# split36_left.net
KiCad netlist of a schematic drawn in EasyEDA Pro
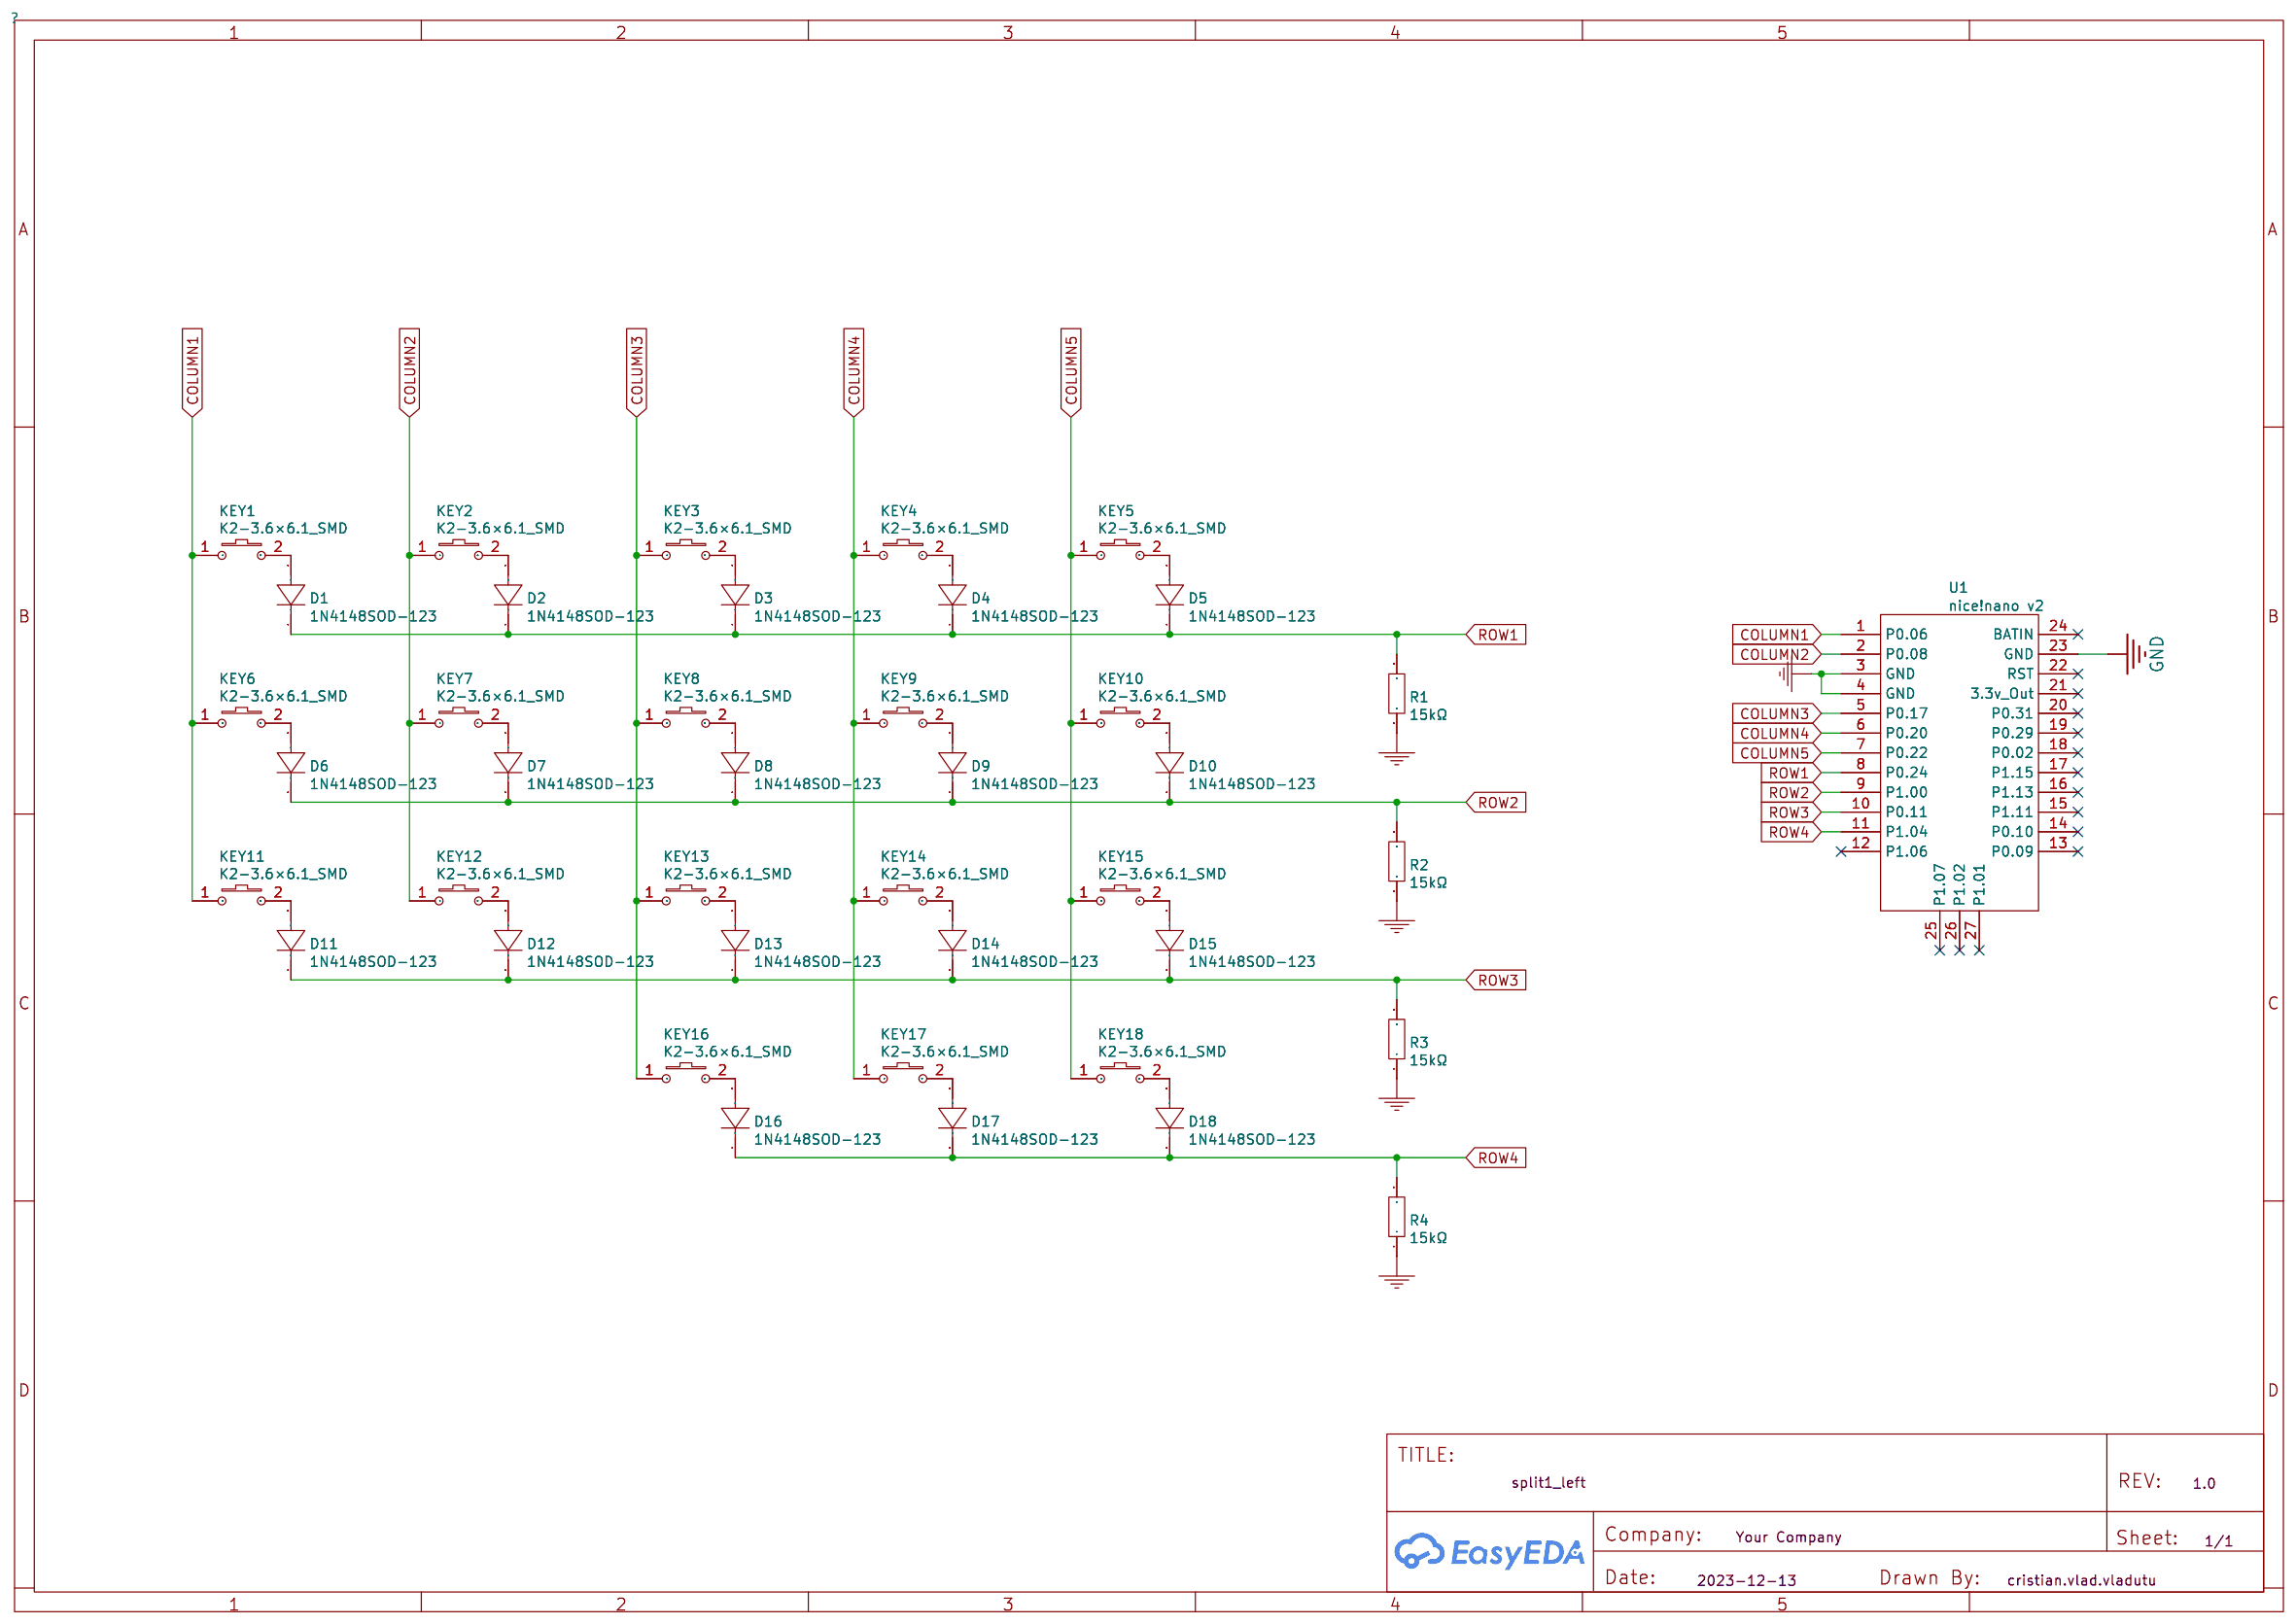
[diagram p0: schematic sheet]

(export (version "E")
  (design (tool "Eeschema 10.0.6"))
  (components
    (comp (ref "D1")
      (value "1N4148SOD-123")
      (footprint "easyedapro:SOD-123_L2.6-W1.6-LS3.5-RD")
      (fields (field (name "Manufacturer") "JKSEMI(金开盛)"))
      (libsource (lib "easyedapro") (part "1N4148SOD-123"))
    )
    (comp (ref "D2")
      (value "1N4148SOD-123")
      (footprint "easyedapro:SOD-123_L2.6-W1.6-LS3.5-RD")
      (fields (field (name "Manufacturer") "JKSEMI(金开盛)"))
      (libsource (lib "easyedapro") (part "1N4148SOD-123"))
    )
    (comp (ref "D3")
      (value "1N4148SOD-123")
      (footprint "easyedapro:SOD-123_L2.6-W1.6-LS3.5-RD")
      (fields (field (name "Manufacturer") "JKSEMI(金开盛)"))
      (libsource (lib "easyedapro") (part "1N4148SOD-123"))
    )
    (comp (ref "D4")
      (value "1N4148SOD-123")
      (footprint "easyedapro:SOD-123_L2.6-W1.6-LS3.5-RD")
      (fields (field (name "Manufacturer") "JKSEMI(金开盛)"))
      (libsource (lib "easyedapro") (part "1N4148SOD-123"))
    )
    (comp (ref "D5")
      (value "1N4148SOD-123")
      (footprint "easyedapro:SOD-123_L2.6-W1.6-LS3.5-RD")
      (fields (field (name "Manufacturer") "JKSEMI(金开盛)"))
      (libsource (lib "easyedapro") (part "1N4148SOD-123"))
    )
    (comp (ref "D6")
      (value "1N4148SOD-123")
      (footprint "easyedapro:SOD-123_L2.6-W1.6-LS3.5-RD")
      (fields (field (name "Manufacturer") "JKSEMI(金开盛)"))
      (libsource (lib "easyedapro") (part "1N4148SOD-123"))
    )
    (comp (ref "D7")
      (value "1N4148SOD-123")
      (footprint "easyedapro:SOD-123_L2.6-W1.6-LS3.5-RD")
      (fields (field (name "Manufacturer") "JKSEMI(金开盛)"))
      (libsource (lib "easyedapro") (part "1N4148SOD-123"))
    )
    (comp (ref "D8")
      (value "1N4148SOD-123")
      (footprint "easyedapro:SOD-123_L2.6-W1.6-LS3.5-RD")
      (fields (field (name "Manufacturer") "JKSEMI(金开盛)"))
      (libsource (lib "easyedapro") (part "1N4148SOD-123"))
    )
    (comp (ref "D9")
      (value "1N4148SOD-123")
      (footprint "easyedapro:SOD-123_L2.6-W1.6-LS3.5-RD")
      (fields (field (name "Manufacturer") "JKSEMI(金开盛)"))
      (libsource (lib "easyedapro") (part "1N4148SOD-123"))
    )
    (comp (ref "D10")
      (value "1N4148SOD-123")
      (footprint "easyedapro:SOD-123_L2.6-W1.6-LS3.5-RD")
      (fields (field (name "Manufacturer") "JKSEMI(金开盛)"))
      (libsource (lib "easyedapro") (part "1N4148SOD-123"))
    )
    (comp (ref "D11")
      (value "1N4148SOD-123")
      (footprint "easyedapro:SOD-123_L2.6-W1.6-LS3.5-RD")
      (fields (field (name "Manufacturer") "JKSEMI(金开盛)"))
      (libsource (lib "easyedapro") (part "1N4148SOD-123"))
    )
    (comp (ref "D12")
      (value "1N4148SOD-123")
      (footprint "easyedapro:SOD-123_L2.6-W1.6-LS3.5-RD")
      (fields (field (name "Manufacturer") "JKSEMI(金开盛)"))
      (libsource (lib "easyedapro") (part "1N4148SOD-123"))
    )
    (comp (ref "D13")
      (value "1N4148SOD-123")
      (footprint "easyedapro:SOD-123_L2.6-W1.6-LS3.5-RD")
      (fields (field (name "Manufacturer") "JKSEMI(金开盛)"))
      (libsource (lib "easyedapro") (part "1N4148SOD-123"))
    )
    (comp (ref "D14")
      (value "1N4148SOD-123")
      (footprint "easyedapro:SOD-123_L2.6-W1.6-LS3.5-RD")
      (fields (field (name "Manufacturer") "JKSEMI(金开盛)"))
      (libsource (lib "easyedapro") (part "1N4148SOD-123"))
    )
    (comp (ref "D15")
      (value "1N4148SOD-123")
      (footprint "easyedapro:SOD-123_L2.6-W1.6-LS3.5-RD")
      (fields (field (name "Manufacturer") "JKSEMI(金开盛)"))
      (libsource (lib "easyedapro") (part "1N4148SOD-123"))
    )
    (comp (ref "D16")
      (value "1N4148SOD-123")
      (footprint "easyedapro:SOD-123_L2.6-W1.6-LS3.5-RD")
      (fields (field (name "Manufacturer") "JKSEMI(金开盛)"))
      (libsource (lib "easyedapro") (part "1N4148SOD-123"))
    )
    (comp (ref "D17")
      (value "1N4148SOD-123")
      (footprint "easyedapro:SOD-123_L2.6-W1.6-LS3.5-RD")
      (fields (field (name "Manufacturer") "JKSEMI(金开盛)"))
      (libsource (lib "easyedapro") (part "1N4148SOD-123"))
    )
    (comp (ref "D18")
      (value "1N4148SOD-123")
      (footprint "easyedapro:SOD-123_L2.6-W1.6-LS3.5-RD")
      (fields (field (name "Manufacturer") "JKSEMI(金开盛)"))
      (libsource (lib "easyedapro") (part "1N4148SOD-123"))
    )
    (comp (ref "KEY1")
      (value "K2-3.6×6.1_SMD")
      (footprint "easyedapro:GATERON LOW PROFILE SWITCH HOTSWAP LED")
      (fields (field (name "Manufacturer Part") "K2-1107ST-A4SW-06"))
      (libsource (lib "easyedapro") (part "K2-3.6×6.1_SMD"))
    )
    (comp (ref "KEY2")
      (value "K2-3.6×6.1_SMD")
      (footprint "easyedapro:GATERON LOW PROFILE SWITCH HOTSWAP LED")
      (fields (field (name "Manufacturer Part") "K2-1107ST-A4SW-06"))
      (libsource (lib "easyedapro") (part "K2-3.6×6.1_SMD"))
    )
    (comp (ref "KEY3")
      (value "K2-3.6×6.1_SMD")
      (footprint "easyedapro:GATERON LOW PROFILE SWITCH HOTSWAP LED")
      (fields (field (name "Manufacturer Part") "K2-1107ST-A4SW-06"))
      (libsource (lib "easyedapro") (part "K2-3.6×6.1_SMD"))
    )
    (comp (ref "KEY4")
      (value "K2-3.6×6.1_SMD")
      (footprint "easyedapro:GATERON LOW PROFILE SWITCH HOTSWAP LED")
      (fields (field (name "Manufacturer Part") "K2-1107ST-A4SW-06"))
      (libsource (lib "easyedapro") (part "K2-3.6×6.1_SMD"))
    )
    (comp (ref "KEY5")
      (value "K2-3.6×6.1_SMD")
      (footprint "easyedapro:GATERON LOW PROFILE SWITCH HOTSWAP LED")
      (fields (field (name "Manufacturer Part") "K2-1107ST-A4SW-06"))
      (libsource (lib "easyedapro") (part "K2-3.6×6.1_SMD"))
    )
    (comp (ref "KEY6")
      (value "K2-3.6×6.1_SMD")
      (footprint "easyedapro:GATERON LOW PROFILE SWITCH HOTSWAP LED")
      (fields (field (name "Manufacturer Part") "K2-1107ST-A4SW-06"))
      (libsource (lib "easyedapro") (part "K2-3.6×6.1_SMD"))
    )
    (comp (ref "KEY7")
      (value "K2-3.6×6.1_SMD")
      (footprint "easyedapro:GATERON LOW PROFILE SWITCH HOTSWAP LED")
      (fields (field (name "Manufacturer Part") "K2-1107ST-A4SW-06"))
      (libsource (lib "easyedapro") (part "K2-3.6×6.1_SMD"))
    )
    (comp (ref "KEY8")
      (value "K2-3.6×6.1_SMD")
      (footprint "easyedapro:GATERON LOW PROFILE SWITCH HOTSWAP LED")
      (fields (field (name "Manufacturer Part") "K2-1107ST-A4SW-06"))
      (libsource (lib "easyedapro") (part "K2-3.6×6.1_SMD"))
    )
    (comp (ref "KEY9")
      (value "K2-3.6×6.1_SMD")
      (footprint "easyedapro:GATERON LOW PROFILE SWITCH HOTSWAP LED")
      (fields (field (name "Manufacturer Part") "K2-1107ST-A4SW-06"))
      (libsource (lib "easyedapro") (part "K2-3.6×6.1_SMD"))
    )
    (comp (ref "KEY10")
      (value "K2-3.6×6.1_SMD")
      (footprint "easyedapro:GATERON LOW PROFILE SWITCH HOTSWAP LED")
      (fields (field (name "Manufacturer Part") "K2-1107ST-A4SW-06"))
      (libsource (lib "easyedapro") (part "K2-3.6×6.1_SMD"))
    )
    (comp (ref "KEY11")
      (value "K2-3.6×6.1_SMD")
      (footprint "easyedapro:GATERON LOW PROFILE SWITCH HOTSWAP LED")
      (fields (field (name "Manufacturer Part") "K2-1107ST-A4SW-06"))
      (libsource (lib "easyedapro") (part "K2-3.6×6.1_SMD"))
    )
    (comp (ref "KEY12")
      (value "K2-3.6×6.1_SMD")
      (footprint "easyedapro:GATERON LOW PROFILE SWITCH HOTSWAP LED")
      (fields (field (name "Manufacturer Part") "K2-1107ST-A4SW-06"))
      (libsource (lib "easyedapro") (part "K2-3.6×6.1_SMD"))
    )
    (comp (ref "KEY13")
      (value "K2-3.6×6.1_SMD")
      (footprint "easyedapro:GATERON LOW PROFILE SWITCH HOTSWAP LED")
      (fields (field (name "Manufacturer Part") "K2-1107ST-A4SW-06"))
      (libsource (lib "easyedapro") (part "K2-3.6×6.1_SMD"))
    )
    (comp (ref "KEY14")
      (value "K2-3.6×6.1_SMD")
      (footprint "easyedapro:GATERON LOW PROFILE SWITCH HOTSWAP LED")
      (fields (field (name "Manufacturer Part") "K2-1107ST-A4SW-06"))
      (libsource (lib "easyedapro") (part "K2-3.6×6.1_SMD"))
    )
    (comp (ref "KEY15")
      (value "K2-3.6×6.1_SMD")
      (footprint "easyedapro:GATERON LOW PROFILE SWITCH HOTSWAP LED")
      (fields (field (name "Manufacturer Part") "K2-1107ST-A4SW-06"))
      (libsource (lib "easyedapro") (part "K2-3.6×6.1_SMD"))
    )
    (comp (ref "KEY16")
      (value "K2-3.6×6.1_SMD")
      (footprint "easyedapro:GATERON LOW PROFILE SWITCH HOTSWAP LED")
      (fields (field (name "Manufacturer Part") "K2-1107ST-A4SW-06"))
      (libsource (lib "easyedapro") (part "K2-3.6×6.1_SMD"))
    )
    (comp (ref "KEY17")
      (value "K2-3.6×6.1_SMD")
      (footprint "easyedapro:GATERON LOW PROFILE SWITCH HOTSWAP LED")
      (fields (field (name "Manufacturer Part") "K2-1107ST-A4SW-06"))
      (libsource (lib "easyedapro") (part "K2-3.6×6.1_SMD"))
    )
    (comp (ref "KEY18")
      (value "K2-3.6×6.1_SMD")
      (footprint "easyedapro:GATERON LOW PROFILE SWITCH HOTSWAP LED")
      (fields (field (name "Manufacturer Part") "K2-1107ST-A4SW-06"))
      (libsource (lib "easyedapro") (part "K2-3.6×6.1_SMD"))
    )
    (comp (ref "R1")
      (value "15kΩ")
      (footprint "easyedapro:R0402")
      (fields (field (name "Manufacturer Part") "RMC040215K5%N") (field (name "Manufacturer") "Tyohm(幸亚电阻)"))
      (libsource (lib "easyedapro") (part "15kΩ"))
    )
    (comp (ref "R2")
      (value "15kΩ")
      (footprint "easyedapro:R0402")
      (fields (field (name "Manufacturer Part") "RMC040215K5%N") (field (name "Manufacturer") "Tyohm(幸亚电阻)"))
      (libsource (lib "easyedapro") (part "15kΩ"))
    )
    (comp (ref "R3")
      (value "15kΩ")
      (footprint "easyedapro:R0402")
      (fields (field (name "Manufacturer Part") "RMC040215K5%N") (field (name "Manufacturer") "Tyohm(幸亚电阻)"))
      (libsource (lib "easyedapro") (part "15kΩ"))
    )
    (comp (ref "R4")
      (value "15kΩ")
      (footprint "easyedapro:R0402")
      (fields (field (name "Manufacturer Part") "RMC040215K5%N") (field (name "Manufacturer") "Tyohm(幸亚电阻)"))
      (libsource (lib "easyedapro") (part "15kΩ"))
    )
    (comp (ref "U1")
      (value "nice!nano v2")
      (footprint "easyedapro:NICE!NANO V2")
      (fields (field (name "Manufacturer") "nice!"))
      (libsource (lib "easyedapro") (part "nice!nano v2"))
    )
  )
  (nets
    (net (code "1") (name "COLUMN1") (class "Default")
      (node (ref "KEY1") (pin "1") (pinfunction "1_1") (pintype "unspecified"))
      (node (ref "KEY11") (pin "1") (pinfunction "1_1") (pintype "unspecified"))
      (node (ref "KEY6") (pin "1") (pinfunction "1_1") (pintype "unspecified"))
      (node (ref "U1") (pin "1") (pinfunction "P0.06_1") (pintype "input"))
    )
    (net (code "2") (name "COLUMN2") (class "Default")
      (node (ref "KEY12") (pin "1") (pinfunction "1_1") (pintype "unspecified"))
      (node (ref "KEY2") (pin "1") (pinfunction "1_1") (pintype "unspecified"))
      (node (ref "KEY7") (pin "1") (pinfunction "1_1") (pintype "unspecified"))
      (node (ref "U1") (pin "2") (pinfunction "P0.08_2") (pintype "input"))
    )
    (net (code "3") (name "COLUMN3") (class "Default")
      (node (ref "KEY13") (pin "1") (pinfunction "1_1") (pintype "unspecified"))
      (node (ref "KEY16") (pin "1") (pinfunction "1_1") (pintype "unspecified"))
      (node (ref "KEY3") (pin "1") (pinfunction "1_1") (pintype "unspecified"))
      (node (ref "KEY8") (pin "1") (pinfunction "1_1") (pintype "unspecified"))
      (node (ref "U1") (pin "5") (pinfunction "P0.17_5") (pintype "unspecified"))
    )
    (net (code "4") (name "COLUMN4") (class "Default")
      (node (ref "KEY14") (pin "1") (pinfunction "1_1") (pintype "unspecified"))
      (node (ref "KEY17") (pin "1") (pinfunction "1_1") (pintype "unspecified"))
      (node (ref "KEY4") (pin "1") (pinfunction "1_1") (pintype "unspecified"))
      (node (ref "KEY9") (pin "1") (pinfunction "1_1") (pintype "unspecified"))
      (node (ref "U1") (pin "6") (pinfunction "P0.20_6") (pintype "unspecified"))
    )
    (net (code "5") (name "COLUMN5") (class "Default")
      (node (ref "KEY10") (pin "1") (pinfunction "1_1") (pintype "unspecified"))
      (node (ref "KEY15") (pin "1") (pinfunction "1_1") (pintype "unspecified"))
      (node (ref "KEY18") (pin "1") (pinfunction "1_1") (pintype "unspecified"))
      (node (ref "KEY5") (pin "1") (pinfunction "1_1") (pintype "unspecified"))
      (node (ref "U1") (pin "7") (pinfunction "P0.22_7") (pintype "unspecified"))
    )
    (net (code "6") (name "GND") (class "Default")
      (node (ref "R1") (pin "1") (pinfunction "1_1") (pintype "unspecified"))
      (node (ref "R2") (pin "1") (pinfunction "1_1") (pintype "unspecified"))
      (node (ref "R3") (pin "1") (pinfunction "1_1") (pintype "unspecified"))
      (node (ref "R4") (pin "1") (pinfunction "1_1") (pintype "unspecified"))
      (node (ref "U1") (pin "23") (pinfunction "GND_23") (pintype "bidirectional"))
      (node (ref "U1") (pin "3") (pinfunction "GND_3") (pintype "unspecified"))
      (node (ref "U1") (pin "4") (pinfunction "GND_4") (pintype "unspecified"))
    )
    (net (code "7") (name "Net-(D1-A)") (class "Default")
      (node (ref "D1") (pin "2") (pinfunction "A_2") (pintype "unspecified"))
      (node (ref "KEY1") (pin "2") (pinfunction "2_2") (pintype "unspecified"))
    )
    (net (code "8") (name "Net-(D2-A)") (class "Default")
      (node (ref "D2") (pin "2") (pinfunction "A_2") (pintype "unspecified"))
      (node (ref "KEY2") (pin "2") (pinfunction "2_2") (pintype "unspecified"))
    )
    (net (code "9") (name "Net-(D3-A)") (class "Default")
      (node (ref "D3") (pin "2") (pinfunction "A_2") (pintype "unspecified"))
      (node (ref "KEY3") (pin "2") (pinfunction "2_2") (pintype "unspecified"))
    )
    (net (code "10") (name "Net-(D4-A)") (class "Default")
      (node (ref "D4") (pin "2") (pinfunction "A_2") (pintype "unspecified"))
      (node (ref "KEY4") (pin "2") (pinfunction "2_2") (pintype "unspecified"))
    )
    (net (code "11") (name "Net-(D5-A)") (class "Default")
      (node (ref "D5") (pin "2") (pinfunction "A_2") (pintype "unspecified"))
      (node (ref "KEY5") (pin "2") (pinfunction "2_2") (pintype "unspecified"))
    )
    (net (code "12") (name "Net-(D6-A)") (class "Default")
      (node (ref "D6") (pin "2") (pinfunction "A_2") (pintype "unspecified"))
      (node (ref "KEY6") (pin "2") (pinfunction "2_2") (pintype "unspecified"))
    )
    (net (code "13") (name "Net-(D7-A)") (class "Default")
      (node (ref "D7") (pin "2") (pinfunction "A_2") (pintype "unspecified"))
      (node (ref "KEY7") (pin "2") (pinfunction "2_2") (pintype "unspecified"))
    )
    (net (code "14") (name "Net-(D8-A)") (class "Default")
      (node (ref "D8") (pin "2") (pinfunction "A_2") (pintype "unspecified"))
      (node (ref "KEY8") (pin "2") (pinfunction "2_2") (pintype "unspecified"))
    )
    (net (code "15") (name "Net-(D9-A)") (class "Default")
      (node (ref "D9") (pin "2") (pinfunction "A_2") (pintype "unspecified"))
      (node (ref "KEY9") (pin "2") (pinfunction "2_2") (pintype "unspecified"))
    )
    (net (code "16") (name "Net-(D10-A)") (class "Default")
      (node (ref "D10") (pin "2") (pinfunction "A_2") (pintype "unspecified"))
      (node (ref "KEY10") (pin "2") (pinfunction "2_2") (pintype "unspecified"))
    )
    (net (code "17") (name "Net-(D11-A)") (class "Default")
      (node (ref "D11") (pin "2") (pinfunction "A_2") (pintype "unspecified"))
      (node (ref "KEY11") (pin "2") (pinfunction "2_2") (pintype "unspecified"))
    )
    (net (code "18") (name "Net-(D12-A)") (class "Default")
      (node (ref "D12") (pin "2") (pinfunction "A_2") (pintype "unspecified"))
      (node (ref "KEY12") (pin "2") (pinfunction "2_2") (pintype "unspecified"))
    )
    (net (code "19") (name "Net-(D13-A)") (class "Default")
      (node (ref "D13") (pin "2") (pinfunction "A_2") (pintype "unspecified"))
      (node (ref "KEY13") (pin "2") (pinfunction "2_2") (pintype "unspecified"))
    )
    (net (code "20") (name "Net-(D14-A)") (class "Default")
      (node (ref "D14") (pin "2") (pinfunction "A_2") (pintype "unspecified"))
      (node (ref "KEY14") (pin "2") (pinfunction "2_2") (pintype "unspecified"))
    )
    (net (code "21") (name "Net-(D15-A)") (class "Default")
      (node (ref "D15") (pin "2") (pinfunction "A_2") (pintype "unspecified"))
      (node (ref "KEY15") (pin "2") (pinfunction "2_2") (pintype "unspecified"))
    )
    (net (code "22") (name "Net-(D16-A)") (class "Default")
      (node (ref "D16") (pin "2") (pinfunction "A_2") (pintype "unspecified"))
      (node (ref "KEY16") (pin "2") (pinfunction "2_2") (pintype "unspecified"))
    )
    (net (code "23") (name "Net-(D17-A)") (class "Default")
      (node (ref "D17") (pin "2") (pinfunction "A_2") (pintype "unspecified"))
      (node (ref "KEY17") (pin "2") (pinfunction "2_2") (pintype "unspecified"))
    )
    (net (code "24") (name "Net-(D18-A)") (class "Default")
      (node (ref "D18") (pin "2") (pinfunction "A_2") (pintype "unspecified"))
      (node (ref "KEY18") (pin "2") (pinfunction "2_2") (pintype "unspecified"))
    )
    (net (code "25") (name "ROW1") (class "Default")
      (node (ref "D1") (pin "1") (pinfunction "K_1") (pintype "unspecified"))
      (node (ref "D2") (pin "1") (pinfunction "K_1") (pintype "unspecified"))
      (node (ref "D3") (pin "1") (pinfunction "K_1") (pintype "unspecified"))
      (node (ref "D4") (pin "1") (pinfunction "K_1") (pintype "unspecified"))
      (node (ref "D5") (pin "1") (pinfunction "K_1") (pintype "unspecified"))
      (node (ref "R1") (pin "2") (pinfunction "2_2") (pintype "unspecified"))
      (node (ref "U1") (pin "8") (pinfunction "P0.24_8") (pintype "unspecified"))
    )
    (net (code "26") (name "ROW2") (class "Default")
      (node (ref "D10") (pin "1") (pinfunction "K_1") (pintype "unspecified"))
      (node (ref "D6") (pin "1") (pinfunction "K_1") (pintype "unspecified"))
      (node (ref "D7") (pin "1") (pinfunction "K_1") (pintype "unspecified"))
      (node (ref "D8") (pin "1") (pinfunction "K_1") (pintype "unspecified"))
      (node (ref "D9") (pin "1") (pinfunction "K_1") (pintype "unspecified"))
      (node (ref "R2") (pin "2") (pinfunction "2_2") (pintype "unspecified"))
      (node (ref "U1") (pin "9") (pinfunction "P1.00_9") (pintype "unspecified"))
    )
    (net (code "27") (name "ROW3") (class "Default")
      (node (ref "D11") (pin "1") (pinfunction "K_1") (pintype "unspecified"))
      (node (ref "D12") (pin "1") (pinfunction "K_1") (pintype "unspecified"))
      (node (ref "D13") (pin "1") (pinfunction "K_1") (pintype "unspecified"))
      (node (ref "D14") (pin "1") (pinfunction "K_1") (pintype "unspecified"))
      (node (ref "D15") (pin "1") (pinfunction "K_1") (pintype "unspecified"))
      (node (ref "R3") (pin "2") (pinfunction "2_2") (pintype "unspecified"))
      (node (ref "U1") (pin "10") (pinfunction "P0.11_10") (pintype "unspecified"))
    )
    (net (code "28") (name "ROW4") (class "Default")
      (node (ref "D16") (pin "1") (pinfunction "K_1") (pintype "unspecified"))
      (node (ref "D17") (pin "1") (pinfunction "K_1") (pintype "unspecified"))
      (node (ref "D18") (pin "1") (pinfunction "K_1") (pintype "unspecified"))
      (node (ref "R4") (pin "2") (pinfunction "2_2") (pintype "unspecified"))
      (node (ref "U1") (pin "11") (pinfunction "P1.04_11") (pintype "unspecified"))
    )
    (net (code "29") (name "unconnected-(U1-3.3v_Out-Pad21)") (class "Default")
      (node (ref "U1") (pin "21") (pinfunction "3.3v_Out_21") (pintype "bidirectional+no_connect"))
    )
    (net (code "30") (name "unconnected-(U1-BATIN-Pad24)") (class "Default")
      (node (ref "U1") (pin "24") (pinfunction "BATIN_24") (pintype "bidirectional+no_connect"))
    )
    (net (code "31") (name "unconnected-(U1-P0.02-Pad18)") (class "Default")
      (node (ref "U1") (pin "18") (pinfunction "P0.02_18") (pintype "bidirectional+no_connect"))
    )
    (net (code "32") (name "unconnected-(U1-P0.09-Pad13)") (class "Default")
      (node (ref "U1") (pin "13") (pinfunction "P0.09_13") (pintype "bidirectional+no_connect"))
    )
    (net (code "33") (name "unconnected-(U1-P0.10-Pad14)") (class "Default")
      (node (ref "U1") (pin "14") (pinfunction "P0.10_14") (pintype "bidirectional+no_connect"))
    )
    (net (code "34") (name "unconnected-(U1-P0.29-Pad19)") (class "Default")
      (node (ref "U1") (pin "19") (pinfunction "P0.29_19") (pintype "bidirectional+no_connect"))
    )
    (net (code "35") (name "unconnected-(U1-P0.31-Pad20)") (class "Default")
      (node (ref "U1") (pin "20") (pinfunction "P0.31_20") (pintype "bidirectional+no_connect"))
    )
    (net (code "36") (name "unconnected-(U1-P1.01-Pad27)") (class "Default")
      (node (ref "U1") (pin "27") (pinfunction "P1.01_27") (pintype "unspecified+no_connect"))
    )
    (net (code "37") (name "unconnected-(U1-P1.02-Pad26)") (class "Default")
      (node (ref "U1") (pin "26") (pinfunction "P1.02_26") (pintype "unspecified+no_connect"))
    )
    (net (code "38") (name "unconnected-(U1-P1.06-Pad12)") (class "Default")
      (node (ref "U1") (pin "12") (pinfunction "P1.06_12") (pintype "unspecified+no_connect"))
    )
    (net (code "39") (name "unconnected-(U1-P1.07-Pad25)") (class "Default")
      (node (ref "U1") (pin "25") (pinfunction "P1.07_25") (pintype "unspecified+no_connect"))
    )
    (net (code "40") (name "unconnected-(U1-P1.11-Pad15)") (class "Default")
      (node (ref "U1") (pin "15") (pinfunction "P1.11_15") (pintype "bidirectional+no_connect"))
    )
    (net (code "41") (name "unconnected-(U1-P1.13-Pad16)") (class "Default")
      (node (ref "U1") (pin "16") (pinfunction "P1.13_16") (pintype "bidirectional+no_connect"))
    )
    (net (code "42") (name "unconnected-(U1-P1.15-Pad17)") (class "Default")
      (node (ref "U1") (pin "17") (pinfunction "P1.15_17") (pintype "bidirectional+no_connect"))
    )
    (net (code "43") (name "unconnected-(U1-RST-Pad22)") (class "Default")
      (node (ref "U1") (pin "22") (pinfunction "RST_22") (pintype "bidirectional+no_connect"))
    )
  )
)
